# lisa_l_low_carrier.net
KiCad netlist of a schematic drawn in EAGLE
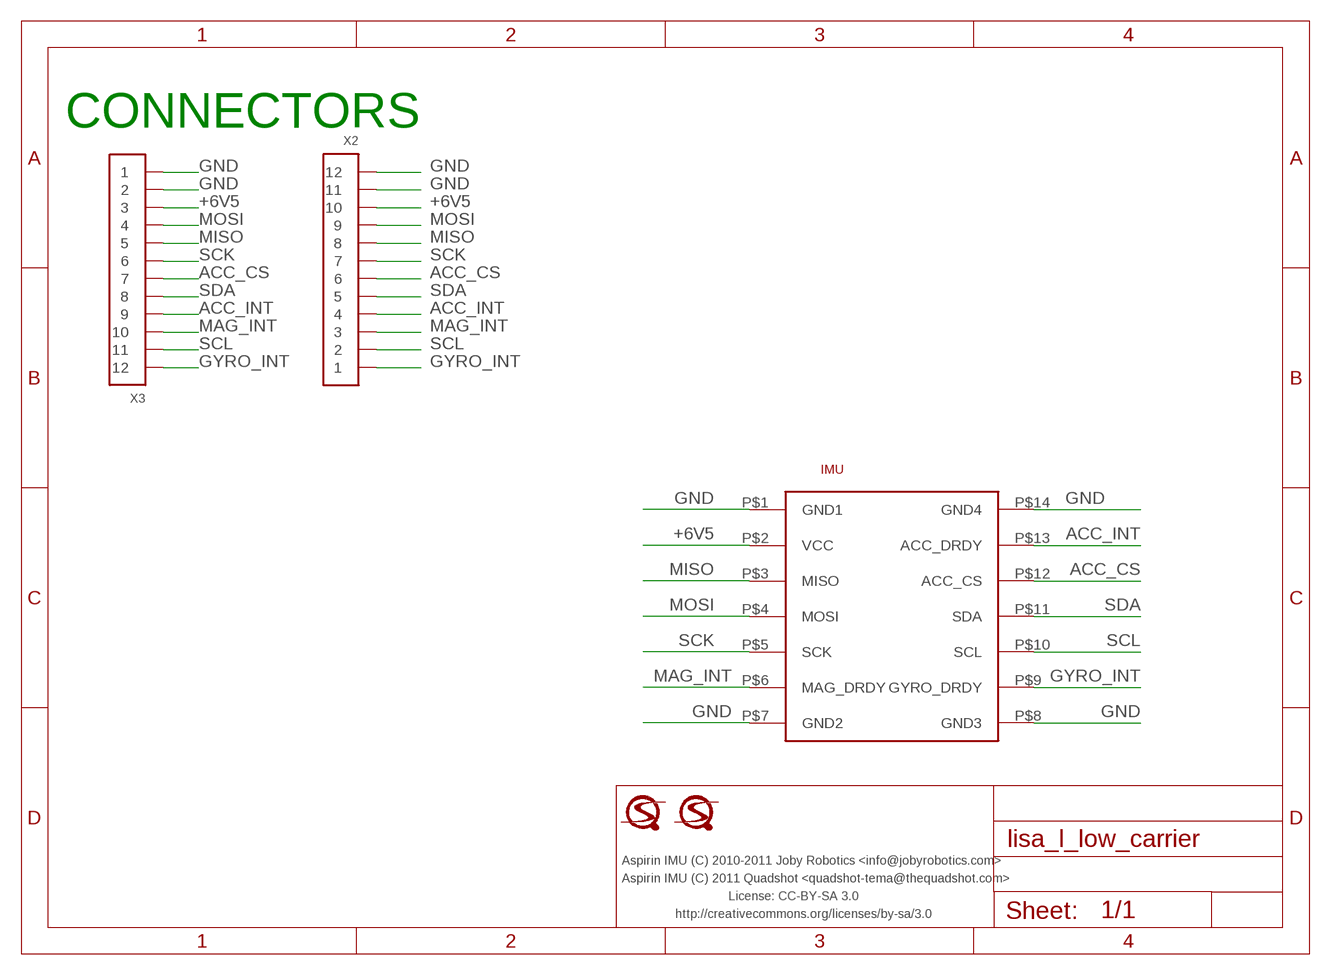
[diagram p0: schematic, sheet 1]

(export (version "E")
  (design (tool "Eeschema 10.0.6"))
  (components
    (comp (ref "IMU")
      (value "ASPIRIN")
      (footprint "eagle-import:ASPIRIN_1")
      (libsource (lib "eagle-import") (part "ASPIRIN"))
    )
    (comp (ref "U$1")
      (value "LOGO")
      (footprint "eagle-import:LOGO")
      (libsource (lib "eagle-import") (part "LOGO"))
    )
    (comp (ref "U$2")
      (value "LOGO")
      (footprint "eagle-import:LOGO")
      (libsource (lib "eagle-import") (part "LOGO"))
    )
    (comp (ref "X2")
      (value "CONN_12-1-53261")
      (footprint "eagle-import:PB-53261-12")
      (libsource (lib "eagle-import") (part "CONN_12-1-53261"))
    )
    (comp (ref "X3")
      (value "CONN_12-1-53047")
      (footprint "eagle-import:PB-53047-12")
      (libsource (lib "eagle-import") (part "CONN_12-1-53047"))
    )
  )
  (nets
    (net (code "1") (name "/+6V5") (class "Default")
      (node (ref "IMU") (pin "P$2") (pinfunction "VCC_P$2") (pintype "bidirectional"))
      (node (ref "X2") (pin "10") (pinfunction "10_10") (pintype "bidirectional"))
      (node (ref "X3") (pin "3") (pinfunction "3_3") (pintype "bidirectional"))
    )
    (net (code "2") (name "/ACC_CS") (class "Default")
      (node (ref "IMU") (pin "P$12") (pinfunction "ACC_CS_P$12") (pintype "bidirectional"))
      (node (ref "X2") (pin "6") (pinfunction "6_6") (pintype "bidirectional"))
      (node (ref "X3") (pin "7") (pinfunction "7_7") (pintype "bidirectional"))
    )
    (net (code "3") (name "/ACC_INT") (class "Default")
      (node (ref "IMU") (pin "P$13") (pinfunction "ACC_DRDY_P$13") (pintype "bidirectional"))
      (node (ref "X2") (pin "4") (pinfunction "4_4") (pintype "bidirectional"))
      (node (ref "X3") (pin "9") (pinfunction "9_9") (pintype "bidirectional"))
    )
    (net (code "4") (name "/GND") (class "Default")
      (node (ref "IMU") (pin "P$1") (pinfunction "GND1_P$1") (pintype "bidirectional"))
      (node (ref "IMU") (pin "P$14") (pinfunction "GND4_P$14") (pintype "bidirectional"))
      (node (ref "IMU") (pin "P$7") (pinfunction "GND2_P$7") (pintype "bidirectional"))
      (node (ref "IMU") (pin "P$8") (pinfunction "GND3_P$8") (pintype "bidirectional"))
      (node (ref "X2") (pin "11") (pinfunction "11_11") (pintype "bidirectional"))
      (node (ref "X2") (pin "12") (pinfunction "12_12") (pintype "bidirectional"))
      (node (ref "X3") (pin "1") (pinfunction "1_1") (pintype "bidirectional"))
      (node (ref "X3") (pin "2") (pinfunction "2_2") (pintype "bidirectional"))
    )
    (net (code "5") (name "/GYRO_INT") (class "Default")
      (node (ref "IMU") (pin "P$9") (pinfunction "GYRO_DRDY_P$9") (pintype "bidirectional"))
      (node (ref "X2") (pin "1") (pinfunction "1_1") (pintype "bidirectional"))
      (node (ref "X3") (pin "12") (pinfunction "12_12") (pintype "bidirectional"))
    )
    (net (code "6") (name "/MAG_INT") (class "Default")
      (node (ref "IMU") (pin "P$6") (pinfunction "MAG_DRDY_P$6") (pintype "bidirectional"))
      (node (ref "X2") (pin "3") (pinfunction "3_3") (pintype "bidirectional"))
      (node (ref "X3") (pin "10") (pinfunction "10_10") (pintype "bidirectional"))
    )
    (net (code "7") (name "/MISO") (class "Default")
      (node (ref "IMU") (pin "P$3") (pinfunction "MISO_P$3") (pintype "bidirectional"))
      (node (ref "X2") (pin "8") (pinfunction "8_8") (pintype "bidirectional"))
      (node (ref "X3") (pin "5") (pinfunction "5_5") (pintype "bidirectional"))
    )
    (net (code "8") (name "/MOSI") (class "Default")
      (node (ref "IMU") (pin "P$4") (pinfunction "MOSI_P$4") (pintype "bidirectional"))
      (node (ref "X2") (pin "9") (pinfunction "9_9") (pintype "bidirectional"))
      (node (ref "X3") (pin "4") (pinfunction "4_4") (pintype "bidirectional"))
    )
    (net (code "9") (name "/SCK") (class "Default")
      (node (ref "IMU") (pin "P$5") (pinfunction "SCK_P$5") (pintype "bidirectional"))
      (node (ref "X2") (pin "7") (pinfunction "7_7") (pintype "bidirectional"))
      (node (ref "X3") (pin "6") (pinfunction "6_6") (pintype "bidirectional"))
    )
    (net (code "10") (name "/SCL") (class "Default")
      (node (ref "IMU") (pin "P$10") (pinfunction "SCL_P$10") (pintype "bidirectional"))
      (node (ref "X2") (pin "2") (pinfunction "2_2") (pintype "bidirectional"))
      (node (ref "X3") (pin "11") (pinfunction "11_11") (pintype "bidirectional"))
    )
    (net (code "11") (name "/SDA") (class "Default")
      (node (ref "IMU") (pin "P$11") (pinfunction "SDA_P$11") (pintype "bidirectional"))
      (node (ref "X2") (pin "5") (pinfunction "5_5") (pintype "bidirectional"))
      (node (ref "X3") (pin "8") (pinfunction "8_8") (pintype "bidirectional"))
    )
  )
)
